# board.net
KiCad netlist of a schematic drawn in EAGLE
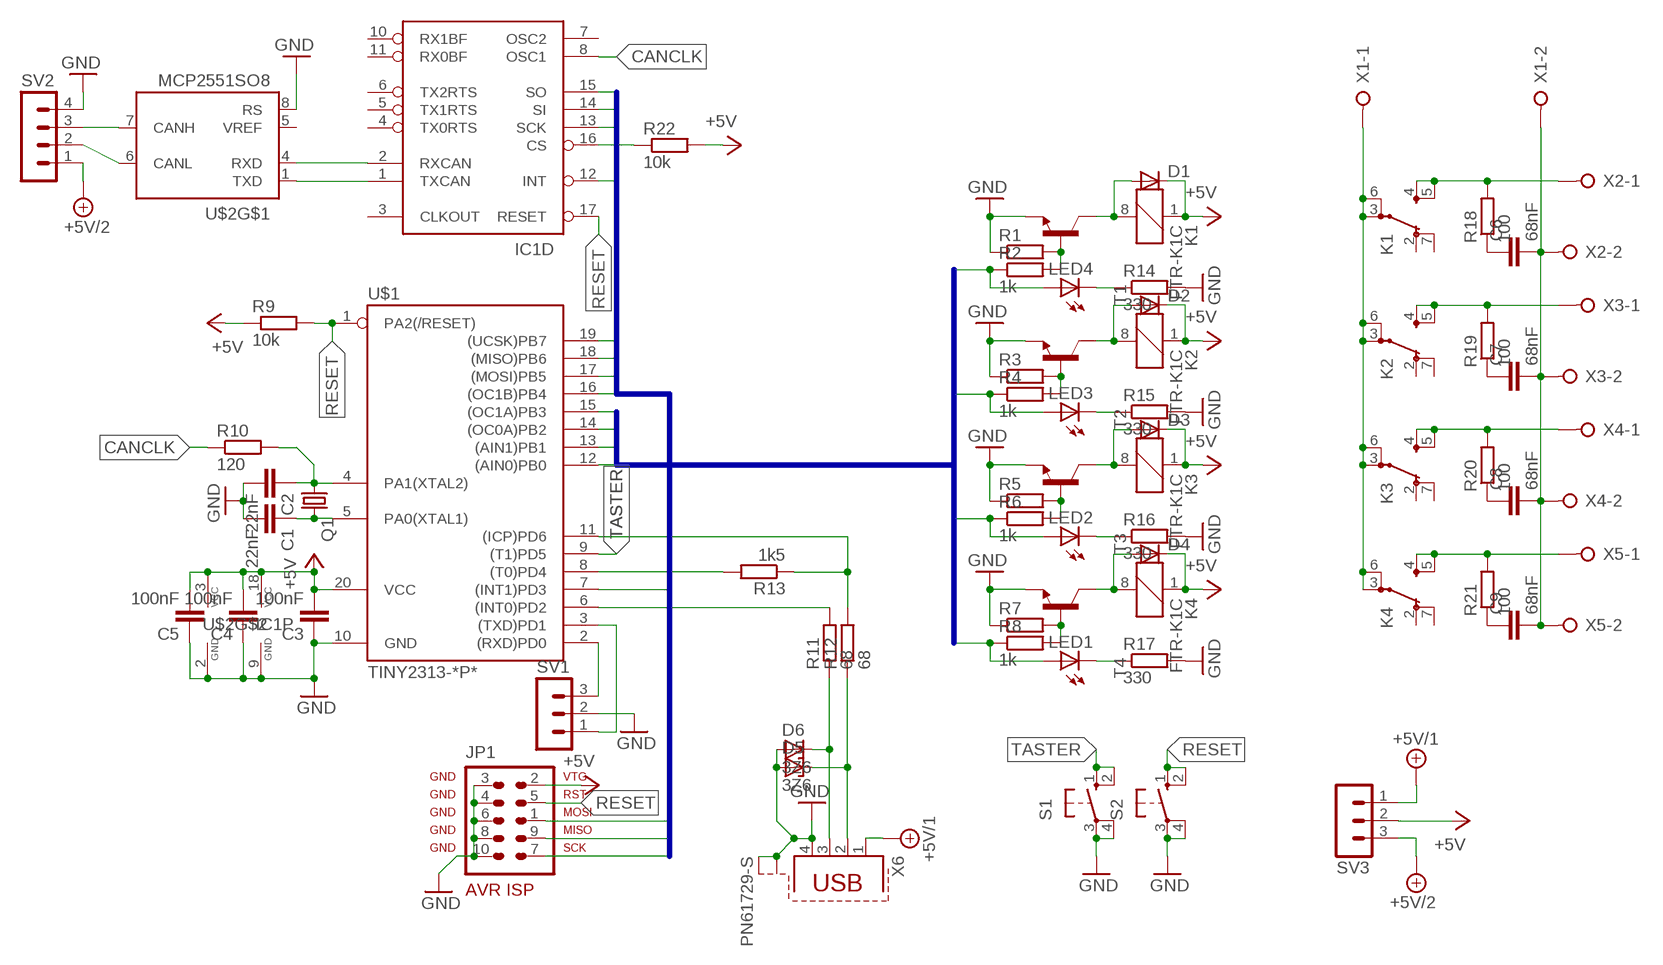
[diagram p0: schematic, sheet 1]

(export (version "E")
  (design (tool "Eeschema 10.0.6"))
  (components
    (comp (ref "C1")
      (value "22nF")
      (footprint "eagle-import:C0805")
      (libsource (lib "eagle-import") (part "C-EUC0805"))
    )
    (comp (ref "C2")
      (value "22nF")
      (footprint "eagle-import:C0805")
      (libsource (lib "eagle-import") (part "C-EUC0805"))
    )
    (comp (ref "C3")
      (value "100nF")
      (footprint "eagle-import:C0805")
      (libsource (lib "eagle-import") (part "C-EUC0805"))
    )
    (comp (ref "C4")
      (value "100nF")
      (footprint "eagle-import:C0805")
      (libsource (lib "eagle-import") (part "C-EUC0805"))
    )
    (comp (ref "C5")
      (value "100nF")
      (footprint "eagle-import:C0805")
      (libsource (lib "eagle-import") (part "C-EUC0805"))
    )
    (comp (ref "C6")
      (value "68nF")
      (footprint "eagle-import:C150-084X183")
      (libsource (lib "eagle-import") (part "C-EU150-084X183"))
    )
    (comp (ref "C7")
      (value "68nF")
      (footprint "eagle-import:C150-084X183")
      (libsource (lib "eagle-import") (part "C-EU150-084X183"))
    )
    (comp (ref "C8")
      (value "68nF")
      (footprint "eagle-import:C150-084X183")
      (libsource (lib "eagle-import") (part "C-EU150-084X183"))
    )
    (comp (ref "C9")
      (value "68nF")
      (footprint "eagle-import:C150-084X183")
      (libsource (lib "eagle-import") (part "C-EU150-084X183"))
    )
    (comp (ref "D1")
      (value "DIODE-DO-214AC")
      (footprint "eagle-import:DO-214AC")
      (libsource (lib "eagle-import") (part "DIODE-DO-214AC"))
    )
    (comp (ref "D2")
      (value "DIODE-DO-214AC")
      (footprint "eagle-import:DO-214AC")
      (libsource (lib "eagle-import") (part "DIODE-DO-214AC"))
    )
    (comp (ref "D3")
      (value "DIODE-DO-214AC")
      (footprint "eagle-import:DO-214AC")
      (libsource (lib "eagle-import") (part "DIODE-DO-214AC"))
    )
    (comp (ref "D4")
      (value "DIODE-DO-214AC")
      (footprint "eagle-import:DO-214AC")
      (libsource (lib "eagle-import") (part "DIODE-DO-214AC"))
    )
    (comp (ref "D5")
      (value "3Z6")
      (footprint "eagle-import:SMB")
      (libsource (lib "eagle-import") (part "ZENER-DIODESMB"))
    )
    (comp (ref "D6")
      (value "3Z6")
      (footprint "eagle-import:SMB")
      (libsource (lib "eagle-import") (part "ZENER-DIODESMB"))
    )
    (comp (ref "IC1")
      (value "MCP2515SO")
      (footprint "eagle-import:SO-18W")
      (libsource (lib "eagle-import") (part "MCP2515SO"))
    )
    (comp (ref "JP1")
      (value "AVR-ISP-10")
      (footprint "eagle-import:AVR-ISP-10")
      (libsource (lib "eagle-import") (part "AVR-ISP-10"))
    )
    (comp (ref "K1")
      (value "FTR-K1C")
      (footprint "eagle-import:FTR-K1C")
      (libsource (lib "eagle-import") (part "FTR-K1C"))
    )
    (comp (ref "K2")
      (value "FTR-K1C")
      (footprint "eagle-import:FTR-K1C")
      (libsource (lib "eagle-import") (part "FTR-K1C"))
    )
    (comp (ref "K3")
      (value "FTR-K1C")
      (footprint "eagle-import:FTR-K1C")
      (libsource (lib "eagle-import") (part "FTR-K1C"))
    )
    (comp (ref "K4")
      (value "FTR-K1C")
      (footprint "eagle-import:FTR-K1C")
      (libsource (lib "eagle-import") (part "FTR-K1C"))
    )
    (comp (ref "LED1")
      (value "LED5MM")
      (footprint "eagle-import:LED5MM")
      (libsource (lib "eagle-import") (part "LED5MM"))
    )
    (comp (ref "LED2")
      (value "LED5MM")
      (footprint "eagle-import:LED5MM")
      (libsource (lib "eagle-import") (part "LED5MM"))
    )
    (comp (ref "LED3")
      (value "LED5MM")
      (footprint "eagle-import:LED5MM")
      (libsource (lib "eagle-import") (part "LED5MM"))
    )
    (comp (ref "LED4")
      (value "LED5MM")
      (footprint "eagle-import:LED5MM")
      (libsource (lib "eagle-import") (part "LED5MM"))
    )
    (comp (ref "Q1")
      (value "CRYSTALHC49U70")
      (footprint "eagle-import:HC49U70")
      (libsource (lib "eagle-import") (part "CRYSTALHC49U70"))
    )
    (comp (ref "R1")
      (value "R-EU_M0805")
      (footprint "eagle-import:M0805")
      (libsource (lib "eagle-import") (part "R-EU_M0805"))
    )
    (comp (ref "R2")
      (value "1k")
      (footprint "eagle-import:M0805")
      (libsource (lib "eagle-import") (part "R-EU_M0805"))
    )
    (comp (ref "R3")
      (value "R-EU_M0805")
      (footprint "eagle-import:M0805")
      (libsource (lib "eagle-import") (part "R-EU_M0805"))
    )
    (comp (ref "R4")
      (value "1k")
      (footprint "eagle-import:M0805")
      (libsource (lib "eagle-import") (part "R-EU_M0805"))
    )
    (comp (ref "R5")
      (value "R-EU_M0805")
      (footprint "eagle-import:M0805")
      (libsource (lib "eagle-import") (part "R-EU_M0805"))
    )
    (comp (ref "R6")
      (value "1k")
      (footprint "eagle-import:M0805")
      (libsource (lib "eagle-import") (part "R-EU_M0805"))
    )
    (comp (ref "R7")
      (value "R-EU_M0805")
      (footprint "eagle-import:M0805")
      (libsource (lib "eagle-import") (part "R-EU_M0805"))
    )
    (comp (ref "R8")
      (value "1k")
      (footprint "eagle-import:M0805")
      (libsource (lib "eagle-import") (part "R-EU_M0805"))
    )
    (comp (ref "R9")
      (value "10k")
      (footprint "eagle-import:M0805")
      (libsource (lib "eagle-import") (part "R-EU_M0805"))
    )
    (comp (ref "R10")
      (value "120")
      (footprint "eagle-import:M0805")
      (libsource (lib "eagle-import") (part "R-EU_M0805"))
    )
    (comp (ref "R11")
      (value "68")
      (footprint "eagle-import:M0805")
      (libsource (lib "eagle-import") (part "R-EU_M0805"))
    )
    (comp (ref "R12")
      (value "68")
      (footprint "eagle-import:M0805")
      (libsource (lib "eagle-import") (part "R-EU_M0805"))
    )
    (comp (ref "R13")
      (value "1k5")
      (footprint "eagle-import:M0805")
      (libsource (lib "eagle-import") (part "R-EU_M0805"))
    )
    (comp (ref "R14")
      (value "330")
      (footprint "eagle-import:M0805")
      (libsource (lib "eagle-import") (part "R-EU_M0805"))
    )
    (comp (ref "R15")
      (value "330")
      (footprint "eagle-import:M0805")
      (libsource (lib "eagle-import") (part "R-EU_M0805"))
    )
    (comp (ref "R16")
      (value "330")
      (footprint "eagle-import:M0805")
      (libsource (lib "eagle-import") (part "R-EU_M0805"))
    )
    (comp (ref "R17")
      (value "330")
      (footprint "eagle-import:M0805")
      (libsource (lib "eagle-import") (part "R-EU_M0805"))
    )
    (comp (ref "R18")
      (value "100")
      (footprint "eagle-import:P0613_15")
      (libsource (lib "eagle-import") (part "R-EU_0613/15"))
    )
    (comp (ref "R19")
      (value "100")
      (footprint "eagle-import:P0613_15")
      (libsource (lib "eagle-import") (part "R-EU_0613/15"))
    )
    (comp (ref "R20")
      (value "100")
      (footprint "eagle-import:P0613_15")
      (libsource (lib "eagle-import") (part "R-EU_0613/15"))
    )
    (comp (ref "R21")
      (value "100")
      (footprint "eagle-import:P0613_15")
      (libsource (lib "eagle-import") (part "R-EU_0613/15"))
    )
    (comp (ref "R22")
      (value "10k")
      (footprint "eagle-import:M0805")
      (libsource (lib "eagle-import") (part "R-EU_M0805"))
    )
    (comp (ref "S1")
      (value "10-XX")
      (footprint "eagle-import:B3F-10XX")
      (fields (field (name "MPN") "B3F-1000"))
      (libsource (lib "eagle-import") (part "10-XX"))
    )
    (comp (ref "S2")
      (value "10-XX")
      (footprint "eagle-import:B3F-10XX")
      (fields (field (name "MPN") "B3F-1000"))
      (libsource (lib "eagle-import") (part "10-XX"))
    )
    (comp (ref "SV1")
      (value "MA03-1")
      (footprint "eagle-import:MA03-1")
      (libsource (lib "eagle-import") (part "MA03-1"))
    )
    (comp (ref "SV2")
      (value "MA04-1")
      (footprint "eagle-import:MA04-1")
      (libsource (lib "eagle-import") (part "MA04-1"))
    )
    (comp (ref "SV3")
      (value "MA03-1")
      (footprint "eagle-import:MA03-1")
      (libsource (lib "eagle-import") (part "MA03-1"))
    )
    (comp (ref "T1")
      (value "-NPN-SOT23-EBC")
      (footprint "eagle-import:SOT23-EBC")
      (libsource (lib "eagle-import") (part "-NPN-SOT23-EBC"))
    )
    (comp (ref "T2")
      (value "-NPN-SOT23-EBC")
      (footprint "eagle-import:SOT23-EBC")
      (libsource (lib "eagle-import") (part "-NPN-SOT23-EBC"))
    )
    (comp (ref "T3")
      (value "-NPN-SOT23-EBC")
      (footprint "eagle-import:SOT23-EBC")
      (libsource (lib "eagle-import") (part "-NPN-SOT23-EBC"))
    )
    (comp (ref "T4")
      (value "-NPN-SOT23-EBC")
      (footprint "eagle-import:SOT23-EBC")
      (libsource (lib "eagle-import") (part "-NPN-SOT23-EBC"))
    )
    (comp (ref "U$1")
      (value "TINY2313-*P*")
      (footprint "eagle-import:DIL20")
      (libsource (lib "eagle-import") (part "TINY2313-P"))
    )
    (comp (ref "U$2")
      (value "MCP2551SO8")
      (footprint "eagle-import:SO08")
      (libsource (lib "eagle-import") (part "MCP2551SO8"))
    )
    (comp (ref "X1")
      (value "W237-02P")
      (footprint "eagle-import:W237-132")
      (libsource (lib "eagle-import") (part "W237-02P"))
    )
    (comp (ref "X2")
      (value "W237-02P")
      (footprint "eagle-import:W237-132")
      (libsource (lib "eagle-import") (part "W237-02P"))
    )
    (comp (ref "X3")
      (value "W237-02P")
      (footprint "eagle-import:W237-132")
      (libsource (lib "eagle-import") (part "W237-02P"))
    )
    (comp (ref "X4")
      (value "W237-02P")
      (footprint "eagle-import:W237-132")
      (libsource (lib "eagle-import") (part "W237-02P"))
    )
    (comp (ref "X5")
      (value "W237-02P")
      (footprint "eagle-import:W237-132")
      (libsource (lib "eagle-import") (part "W237-02P"))
    )
    (comp (ref "X6")
      (value "PN61729-S")
      (footprint "eagle-import:PN61729-S")
      (libsource (lib "eagle-import") (part "PN61729-S"))
    )
  )
  (nets
    (net (code "1") (name "+5V") (class "Default")
      (node (ref "C3") (pin "2") (pinfunction "2_2") (pintype "passive"))
      (node (ref "C4") (pin "2") (pinfunction "2_2") (pintype "passive"))
      (node (ref "C5") (pin "2") (pinfunction "2_2") (pintype "passive"))
      (node (ref "D1") (pin "C") (pinfunction "C_C") (pintype "passive"))
      (node (ref "D2") (pin "C") (pinfunction "C_C") (pintype "passive"))
      (node (ref "D3") (pin "C") (pinfunction "C_C") (pintype "passive"))
      (node (ref "D4") (pin "C") (pinfunction "C_C") (pintype "passive"))
      (node (ref "IC1") (pin "18") (pinfunction "VCC_18") (pintype "power_in"))
      (node (ref "JP1") (pin "2") (pinfunction "2_2") (pintype "passive"))
      (node (ref "K1") (pin "1") (pinfunction "1_1") (pintype "passive"))
      (node (ref "K2") (pin "1") (pinfunction "1_1") (pintype "passive"))
      (node (ref "K3") (pin "1") (pinfunction "1_1") (pintype "passive"))
      (node (ref "K4") (pin "1") (pinfunction "1_1") (pintype "passive"))
      (node (ref "R22") (pin "2") (pinfunction "2_2") (pintype "passive"))
      (node (ref "R9") (pin "1") (pinfunction "1_1") (pintype "passive"))
      (node (ref "SV3") (pin "2") (pinfunction "2_2") (pintype "passive"))
      (node (ref "U$1") (pin "20") (pinfunction "VCC_20") (pintype "power_in"))
      (node (ref "U$2") (pin "3") (pinfunction "VCC_3") (pintype "power_in"))
    )
    (net (code "2") (name "+5V{slash}1") (class "Default")
      (node (ref "SV3") (pin "1") (pinfunction "1_1") (pintype "passive"))
      (node (ref "X6") (pin "1") (pinfunction "1_1") (pintype "passive"))
    )
    (net (code "3") (name "+5V{slash}2") (class "Default")
      (node (ref "SV2") (pin "1") (pinfunction "1_1") (pintype "passive"))
      (node (ref "SV3") (pin "3") (pinfunction "3_3") (pintype "passive"))
    )
    (net (code "4") (name "/CS") (class "Default")
      (node (ref "IC1") (pin "16") (pinfunction "CS_16") (pintype "input"))
      (node (ref "R22") (pin "1") (pinfunction "1_1") (pintype "passive"))
      (node (ref "U$1") (pin "16") (pinfunction "(OC1B)PB4_16") (pintype "bidirectional"))
    )
    (net (code "5") (name "/INT") (class "Default")
      (node (ref "IC1") (pin "12") (pinfunction "INT_12") (pintype "output"))
      (node (ref "U$1") (pin "7") (pinfunction "(INT1)PD3_7") (pintype "bidirectional"))
    )
    (net (code "6") (name "/MISO") (class "Default")
      (node (ref "IC1") (pin "15") (pinfunction "SO_15") (pintype "output"))
      (node (ref "JP1") (pin "9") (pinfunction "9_9") (pintype "passive"))
      (node (ref "U$1") (pin "18") (pinfunction "(MISO)PB6_18") (pintype "bidirectional"))
    )
    (net (code "7") (name "/MOSI") (class "Default")
      (node (ref "IC1") (pin "14") (pinfunction "SI_14") (pintype "input"))
      (node (ref "JP1") (pin "1") (pinfunction "1_1") (pintype "passive"))
      (node (ref "U$1") (pin "17") (pinfunction "(MOSI)PB5_17") (pintype "bidirectional"))
    )
    (net (code "8") (name "/RELAI0") (class "Default")
      (node (ref "LED1") (pin "A") (pinfunction "A_A") (pintype "passive"))
      (node (ref "R8") (pin "1") (pinfunction "1_1") (pintype "passive"))
      (node (ref "U$1") (pin "12") (pinfunction "(AIN0)PB0_12") (pintype "bidirectional"))
    )
    (net (code "9") (name "/RELAI1") (class "Default")
      (node (ref "LED2") (pin "A") (pinfunction "A_A") (pintype "passive"))
      (node (ref "R6") (pin "1") (pinfunction "1_1") (pintype "passive"))
      (node (ref "U$1") (pin "13") (pinfunction "(AIN1)PB1_13") (pintype "bidirectional"))
    )
    (net (code "10") (name "/RELAI2") (class "Default")
      (node (ref "LED3") (pin "A") (pinfunction "A_A") (pintype "passive"))
      (node (ref "R4") (pin "1") (pinfunction "1_1") (pintype "passive"))
      (node (ref "U$1") (pin "14") (pinfunction "(OC0A)PB2_14") (pintype "bidirectional"))
    )
    (net (code "11") (name "/RELAI3") (class "Default")
      (node (ref "LED4") (pin "A") (pinfunction "A_A") (pintype "passive"))
      (node (ref "R2") (pin "1") (pinfunction "1_1") (pintype "passive"))
      (node (ref "U$1") (pin "15") (pinfunction "(OC1A)PB3_15") (pintype "bidirectional"))
    )
    (net (code "12") (name "/SCK") (class "Default")
      (node (ref "IC1") (pin "13") (pinfunction "SCK_13") (pintype "input"))
      (node (ref "JP1") (pin "7") (pinfunction "7_7") (pintype "passive"))
      (node (ref "U$1") (pin "19") (pinfunction "(UCSK)PB7_19") (pintype "bidirectional"))
    )
    (net (code "13") (name "CANCLK") (class "Default")
      (node (ref "IC1") (pin "8") (pinfunction "OSC1_8") (pintype "input"))
      (node (ref "R10") (pin "1") (pinfunction "1_1") (pintype "passive"))
    )
    (net (code "14") (name "GND") (class "Default")
      (node (ref "C1") (pin "2") (pinfunction "2_2") (pintype "passive"))
      (node (ref "C2") (pin "2") (pinfunction "2_2") (pintype "passive"))
      (node (ref "C3") (pin "1") (pinfunction "1_1") (pintype "passive"))
      (node (ref "C4") (pin "1") (pinfunction "1_1") (pintype "passive"))
      (node (ref "C5") (pin "1") (pinfunction "1_1") (pintype "passive"))
      (node (ref "D5") (pin "A") (pinfunction "A_A") (pintype "passive"))
      (node (ref "D6") (pin "A") (pinfunction "A_A") (pintype "passive"))
      (node (ref "IC1") (pin "9") (pinfunction "GND_9") (pintype "power_in"))
      (node (ref "JP1") (pin "10") (pinfunction "10_10") (pintype "passive"))
      (node (ref "JP1") (pin "3") (pinfunction "3_3") (pintype "passive"))
      (node (ref "JP1") (pin "4") (pinfunction "4_4") (pintype "passive"))
      (node (ref "JP1") (pin "6") (pinfunction "6_6") (pintype "passive"))
      (node (ref "JP1") (pin "8") (pinfunction "8_8") (pintype "passive"))
      (node (ref "R1") (pin "1") (pinfunction "1_1") (pintype "passive"))
      (node (ref "R14") (pin "2") (pinfunction "2_2") (pintype "passive"))
      (node (ref "R15") (pin "2") (pinfunction "2_2") (pintype "passive"))
      (node (ref "R16") (pin "2") (pinfunction "2_2") (pintype "passive"))
      (node (ref "R17") (pin "2") (pinfunction "2_2") (pintype "passive"))
      (node (ref "R3") (pin "1") (pinfunction "1_1") (pintype "passive"))
      (node (ref "R5") (pin "1") (pinfunction "1_1") (pintype "passive"))
      (node (ref "R7") (pin "1") (pinfunction "1_1") (pintype "passive"))
      (node (ref "S1") (pin "3") (pinfunction "P_3") (pintype "passive"))
      (node (ref "S1") (pin "4") (pinfunction "P1_4") (pintype "passive"))
      (node (ref "S2") (pin "3") (pinfunction "P_3") (pintype "passive"))
      (node (ref "S2") (pin "4") (pinfunction "P1_4") (pintype "passive"))
      (node (ref "SV1") (pin "2") (pinfunction "2_2") (pintype "passive"))
      (node (ref "SV2") (pin "4") (pinfunction "4_4") (pintype "passive"))
      (node (ref "T1") (pin "E") (pinfunction "E_E") (pintype "passive"))
      (node (ref "T2") (pin "E") (pinfunction "E_E") (pintype "passive"))
      (node (ref "T3") (pin "E") (pinfunction "E_E") (pintype "passive"))
      (node (ref "T4") (pin "E") (pinfunction "E_E") (pintype "passive"))
      (node (ref "U$1") (pin "10") (pinfunction "GND_10") (pintype "power_in"))
      (node (ref "U$2") (pin "2") (pinfunction "GND_2") (pintype "power_in"))
      (node (ref "U$2") (pin "8") (pinfunction "RS_8") (pintype "bidirectional"))
      (node (ref "X6") (pin "4") (pinfunction "4_4") (pintype "passive"))
      (node (ref "X6") (pin "S1") (pinfunction "S1_S1") (pintype "passive"))
      (node (ref "X6") (pin "S2") (pinfunction "S2_S2") (pintype "passive"))
    )
    (net (code "15") (name "Net-(C6-Pad1)") (class "Default")
      (node (ref "C6") (pin "1") (pinfunction "1_1") (pintype "passive"))
      (node (ref "R18") (pin "1") (pinfunction "1_1") (pintype "passive"))
    )
    (net (code "16") (name "Net-(C7-Pad1)") (class "Default")
      (node (ref "C7") (pin "1") (pinfunction "1_1") (pintype "passive"))
      (node (ref "R19") (pin "1") (pinfunction "1_1") (pintype "passive"))
    )
    (net (code "17") (name "Net-(C8-Pad1)") (class "Default")
      (node (ref "C8") (pin "1") (pinfunction "1_1") (pintype "passive"))
      (node (ref "R20") (pin "1") (pinfunction "1_1") (pintype "passive"))
    )
    (net (code "18") (name "Net-(C9-Pad1)") (class "Default")
      (node (ref "C9") (pin "1") (pinfunction "1_1") (pintype "passive"))
      (node (ref "R21") (pin "1") (pinfunction "1_1") (pintype "passive"))
    )
    (net (code "19") (name "Net-(D5-PadC)") (class "Default")
      (node (ref "D5") (pin "C") (pinfunction "C_C") (pintype "passive"))
      (node (ref "R12") (pin "1") (pinfunction "1_1") (pintype "passive"))
      (node (ref "X6") (pin "2") (pinfunction "2_2") (pintype "passive"))
    )
    (net (code "20") (name "Net-(D6-PadC)") (class "Default")
      (node (ref "D6") (pin "C") (pinfunction "C_C") (pintype "passive"))
      (node (ref "R11") (pin "1") (pinfunction "1_1") (pintype "passive"))
      (node (ref "X6") (pin "3") (pinfunction "3_3") (pintype "passive"))
    )
    (net (code "21") (name "Net-(IC1A-RXCAN)") (class "Default")
      (node (ref "IC1") (pin "2") (pinfunction "RXCAN_2") (pintype "input"))
      (node (ref "U$2") (pin "4") (pinfunction "RXD_4") (pintype "bidirectional"))
    )
    (net (code "22") (name "Net-(IC1A-TXCAN)") (class "Default")
      (node (ref "IC1") (pin "1") (pinfunction "TXCAN_1") (pintype "output"))
      (node (ref "U$2") (pin "1") (pinfunction "TXD_1") (pintype "bidirectional"))
    )
    (net (code "23") (name "Net-(K1A-PA)") (class "Default")
      (node (ref "K1") (pin "3") (pinfunction "PA_3") (pintype "passive"))
      (node (ref "K1") (pin "6") (pinfunction "PB_6") (pintype "passive"))
      (node (ref "K2") (pin "3") (pinfunction "PA_3") (pintype "passive"))
      (node (ref "K2") (pin "6") (pinfunction "PB_6") (pintype "passive"))
      (node (ref "K3") (pin "3") (pinfunction "PA_3") (pintype "passive"))
      (node (ref "K3") (pin "6") (pinfunction "PB_6") (pintype "passive"))
      (node (ref "K4") (pin "3") (pinfunction "PA_3") (pintype "passive"))
      (node (ref "K4") (pin "6") (pinfunction "PB_6") (pintype "passive"))
      (node (ref "X1") (pin "1") (pinfunction "KL_1") (pintype "passive"))
    )
    (net (code "24") (name "Net-(K1A-SA)") (class "Default")
      (node (ref "K1") (pin "4") (pinfunction "SA_4") (pintype "passive"))
      (node (ref "K1") (pin "5") (pinfunction "SB_5") (pintype "passive"))
      (node (ref "R18") (pin "2") (pinfunction "2_2") (pintype "passive"))
      (node (ref "X2") (pin "1") (pinfunction "KL_1") (pintype "passive"))
    )
    (net (code "25") (name "Net-(K1B-2)") (class "Default")
      (node (ref "D1") (pin "A") (pinfunction "A_A") (pintype "passive"))
      (node (ref "K1") (pin "8") (pinfunction "2_8") (pintype "passive"))
      (node (ref "T1") (pin "C") (pinfunction "C_C") (pintype "passive"))
    )
    (net (code "26") (name "Net-(K2A-SA)") (class "Default")
      (node (ref "K2") (pin "4") (pinfunction "SA_4") (pintype "passive"))
      (node (ref "K2") (pin "5") (pinfunction "SB_5") (pintype "passive"))
      (node (ref "R19") (pin "2") (pinfunction "2_2") (pintype "passive"))
      (node (ref "X3") (pin "1") (pinfunction "KL_1") (pintype "passive"))
    )
    (net (code "27") (name "Net-(K2B-2)") (class "Default")
      (node (ref "D2") (pin "A") (pinfunction "A_A") (pintype "passive"))
      (node (ref "K2") (pin "8") (pinfunction "2_8") (pintype "passive"))
      (node (ref "T2") (pin "C") (pinfunction "C_C") (pintype "passive"))
    )
    (net (code "28") (name "Net-(K3A-SA)") (class "Default")
      (node (ref "K3") (pin "4") (pinfunction "SA_4") (pintype "passive"))
      (node (ref "K3") (pin "5") (pinfunction "SB_5") (pintype "passive"))
      (node (ref "R20") (pin "2") (pinfunction "2_2") (pintype "passive"))
      (node (ref "X4") (pin "1") (pinfunction "KL_1") (pintype "passive"))
    )
    (net (code "29") (name "Net-(K3B-2)") (class "Default")
      (node (ref "D3") (pin "A") (pinfunction "A_A") (pintype "passive"))
      (node (ref "K3") (pin "8") (pinfunction "2_8") (pintype "passive"))
      (node (ref "T3") (pin "C") (pinfunction "C_C") (pintype "passive"))
    )
    (net (code "30") (name "Net-(K4A-SA)") (class "Default")
      (node (ref "K4") (pin "4") (pinfunction "SA_4") (pintype "passive"))
      (node (ref "K4") (pin "5") (pinfunction "SB_5") (pintype "passive"))
      (node (ref "R21") (pin "2") (pinfunction "2_2") (pintype "passive"))
      (node (ref "X5") (pin "1") (pinfunction "KL_1") (pintype "passive"))
    )
    (net (code "31") (name "Net-(K4B-2)") (class "Default")
      (node (ref "D4") (pin "A") (pinfunction "A_A") (pintype "passive"))
      (node (ref "K4") (pin "8") (pinfunction "2_8") (pintype "passive"))
      (node (ref "T4") (pin "C") (pinfunction "C_C") (pintype "passive"))
    )
    (net (code "32") (name "Net-(LED1-C)") (class "Default")
      (node (ref "LED1") (pin "K") (pinfunction "C_K") (pintype "passive"))
      (node (ref "R17") (pin "1") (pinfunction "1_1") (pintype "passive"))
    )
    (net (code "33") (name "Net-(LED2-C)") (class "Default")
      (node (ref "LED2") (pin "K") (pinfunction "C_K") (pintype "passive"))
      (node (ref "R16") (pin "1") (pinfunction "1_1") (pintype "passive"))
    )
    (net (code "34") (name "Net-(LED3-C)") (class "Default")
      (node (ref "LED3") (pin "K") (pinfunction "C_K") (pintype "passive"))
      (node (ref "R15") (pin "1") (pinfunction "1_1") (pintype "passive"))
    )
    (net (code "35") (name "Net-(LED4-C)") (class "Default")
      (node (ref "LED4") (pin "K") (pinfunction "C_K") (pintype "passive"))
      (node (ref "R14") (pin "1") (pinfunction "1_1") (pintype "passive"))
    )
    (net (code "36") (name "Net-(R1-Pad2)") (class "Default")
      (node (ref "R1") (pin "2") (pinfunction "2_2") (pintype "passive"))
      (node (ref "R2") (pin "2") (pinfunction "2_2") (pintype "passive"))
      (node (ref "T1") (pin "B") (pinfunction "B_B") (pintype "passive"))
    )
    (net (code "37") (name "Net-(R3-Pad2)") (class "Default")
      (node (ref "R3") (pin "2") (pinfunction "2_2") (pintype "passive"))
      (node (ref "R4") (pin "2") (pinfunction "2_2") (pintype "passive"))
      (node (ref "T2") (pin "B") (pinfunction "B_B") (pintype "passive"))
    )
    (net (code "38") (name "Net-(R5-Pad2)") (class "Default")
      (node (ref "R5") (pin "2") (pinfunction "2_2") (pintype "passive"))
      (node (ref "R6") (pin "2") (pinfunction "2_2") (pintype "passive"))
      (node (ref "T3") (pin "B") (pinfunction "B_B") (pintype "passive"))
    )
    (net (code "39") (name "Net-(R7-Pad2)") (class "Default")
      (node (ref "R7") (pin "2") (pinfunction "2_2") (pintype "passive"))
      (node (ref "R8") (pin "2") (pinfunction "2_2") (pintype "passive"))
      (node (ref "T4") (pin "B") (pinfunction "B_B") (pintype "passive"))
    )
    (net (code "40") (name "Net-(U$1-(ICP)PD6)") (class "Default")
      (node (ref "R12") (pin "2") (pinfunction "2_2") (pintype "passive"))
      (node (ref "R13") (pin "1") (pinfunction "1_1") (pintype "passive"))
      (node (ref "U$1") (pin "11") (pinfunction "(ICP)PD6_11") (pintype "bidirectional"))
    )
    (net (code "41") (name "Net-(U$1-(INT0)PD2)") (class "Default")
      (node (ref "R11") (pin "2") (pinfunction "2_2") (pintype "passive"))
      (node (ref "U$1") (pin "6") (pinfunction "(INT0)PD2_6") (pintype "bidirectional"))
    )
    (net (code "42") (name "Net-(U$1-(RXD)PD0)") (class "Default")
      (node (ref "SV1") (pin "3") (pinfunction "3_3") (pintype "passive"))
      (node (ref "U$1") (pin "2") (pinfunction "(RXD)PD0_2") (pintype "bidirectional"))
    )
    (net (code "43") (name "Net-(U$1-(T0)PD4)") (class "Default")
      (node (ref "R13") (pin "2") (pinfunction "2_2") (pintype "passive"))
      (node (ref "U$1") (pin "8") (pinfunction "(T0)PD4_8") (pintype "bidirectional"))
    )
    (net (code "44") (name "Net-(U$1-(TXD)PD1)") (class "Default")
      (node (ref "SV1") (pin "1") (pinfunction "1_1") (pintype "passive"))
      (node (ref "U$1") (pin "3") (pinfunction "(TXD)PD1_3") (pintype "bidirectional"))
    )
    (net (code "45") (name "Net-(U$1-PA0(XTAL1))") (class "Default")
      (node (ref "C1") (pin "1") (pinfunction "1_1") (pintype "passive"))
      (node (ref "Q1") (pin "2") (pinfunction "2_2") (pintype "passive"))
      (node (ref "U$1") (pin "5") (pinfunction "PA0(XTAL1)_5") (pintype "bidirectional"))
    )
    (net (code "46") (name "Net-(U$1-PA1(XTAL2))") (class "Default")
      (node (ref "C2") (pin "1") (pinfunction "1_1") (pintype "passive"))
      (node (ref "Q1") (pin "1") (pinfunction "1_1") (pintype "passive"))
      (node (ref "R10") (pin "2") (pinfunction "2_2") (pintype "passive"))
      (node (ref "U$1") (pin "4") (pinfunction "PA1(XTAL2)_4") (pintype "bidirectional"))
    )
    (net (code "47") (name "Net-(U$2A-CANH)") (class "Default")
      (node (ref "SV2") (pin "3") (pinfunction "3_3") (pintype "passive"))
      (node (ref "U$2") (pin "7") (pinfunction "CANH_7") (pintype "bidirectional"))
    )
    (net (code "48") (name "Net-(U$2A-CANL)") (class "Default")
      (node (ref "SV2") (pin "2") (pinfunction "2_2") (pintype "passive"))
      (node (ref "U$2") (pin "6") (pinfunction "CANL_6") (pintype "bidirectional"))
    )
    (net (code "49") (name "Net-(X1B-KL)") (class "Default")
      (node (ref "C6") (pin "2") (pinfunction "2_2") (pintype "passive"))
      (node (ref "C7") (pin "2") (pinfunction "2_2") (pintype "passive"))
      (node (ref "C8") (pin "2") (pinfunction "2_2") (pintype "passive"))
      (node (ref "C9") (pin "2") (pinfunction "2_2") (pintype "passive"))
      (node (ref "X1") (pin "2") (pinfunction "KL_2") (pintype "passive"))
      (node (ref "X2") (pin "2") (pinfunction "KL_2") (pintype "passive"))
      (node (ref "X3") (pin "2") (pinfunction "KL_2") (pintype "passive"))
      (node (ref "X4") (pin "2") (pinfunction "KL_2") (pintype "passive"))
      (node (ref "X5") (pin "2") (pinfunction "KL_2") (pintype "passive"))
    )
    (net (code "50") (name "RESET") (class "Default")
      (node (ref "IC1") (pin "17") (pinfunction "RESET_17") (pintype "input"))
      (node (ref "JP1") (pin "5") (pinfunction "5_5") (pintype "passive"))
      (node (ref "R9") (pin "2") (pinfunction "2_2") (pintype "passive"))
      (node (ref "S2") (pin "1") (pinfunction "S_1") (pintype "passive"))
      (node (ref "S2") (pin "2") (pinfunction "S1_2") (pintype "passive"))
      (node (ref "U$1") (pin "1") (pinfunction "PA2(/RESET)_1") (pintype "input"))
    )
    (net (code "51") (name "TASTER") (class "Default")
      (node (ref "S1") (pin "1") (pinfunction "S_1") (pintype "passive"))
      (node (ref "S1") (pin "2") (pinfunction "S1_2") (pintype "passive"))
      (node (ref "U$1") (pin "9") (pinfunction "(T1)PD5_9") (pintype "bidirectional"))
    )
    (net (code "52") (name "unconnected-(IC1A-CLKOUT-Pad3)") (class "Default")
      (node (ref "IC1") (pin "3") (pinfunction "CLKOUT_3") (pintype "output"))
    )
    (net (code "53") (name "unconnected-(IC1A-OSC2-Pad7)") (class "Default")
      (node (ref "IC1") (pin "7") (pinfunction "OSC2_7") (pintype "input"))
    )
    (net (code "54") (name "unconnected-(IC1A-RX0BF-Pad11)") (class "Default")
      (node (ref "IC1") (pin "11") (pinfunction "RX0BF_11") (pintype "output"))
    )
    (net (code "55") (name "unconnected-(IC1A-RX1BF-Pad10)") (class "Default")
      (node (ref "IC1") (pin "10") (pinfunction "RX1BF_10") (pintype "output"))
    )
    (net (code "56") (name "unconnected-(IC1A-TX0RTS-Pad4)") (class "Default")
      (node (ref "IC1") (pin "4") (pinfunction "TX0RTS_4") (pintype "input"))
    )
    (net (code "57") (name "unconnected-(IC1A-TX1RTS-Pad5)") (class "Default")
      (node (ref "IC1") (pin "5") (pinfunction "TX1RTS_5") (pintype "input"))
    )
    (net (code "58") (name "unconnected-(IC1A-TX2RTS-Pad6)") (class "Default")
      (node (ref "IC1") (pin "6") (pinfunction "TX2RTS_6") (pintype "input"))
    )
    (net (code "59") (name "unconnected-(K1A-OA-Pad2)") (class "Default")
      (node (ref "K1") (pin "2") (pinfunction "OA_2") (pintype "passive"))
    )
    (net (code "60") (name "unconnected-(K1A-OB-Pad7)") (class "Default")
      (node (ref "K1") (pin "7") (pinfunction "OB_7") (pintype "passive"))
    )
    (net (code "61") (name "unconnected-(K2A-OA-Pad2)") (class "Default")
      (node (ref "K2") (pin "2") (pinfunction "OA_2") (pintype "passive"))
    )
    (net (code "62") (name "unconnected-(K2A-OB-Pad7)") (class "Default")
      (node (ref "K2") (pin "7") (pinfunction "OB_7") (pintype "passive"))
    )
    (net (code "63") (name "unconnected-(K3A-OA-Pad2)") (class "Default")
      (node (ref "K3") (pin "2") (pinfunction "OA_2") (pintype "passive"))
    )
    (net (code "64") (name "unconnected-(K3A-OB-Pad7)") (class "Default")
      (node (ref "K3") (pin "7") (pinfunction "OB_7") (pintype "passive"))
    )
    (net (code "65") (name "unconnected-(K4A-OA-Pad2)") (class "Default")
      (node (ref "K4") (pin "2") (pinfunction "OA_2") (pintype "passive"))
    )
    (net (code "66") (name "unconnected-(K4A-OB-Pad7)") (class "Default")
      (node (ref "K4") (pin "7") (pinfunction "OB_7") (pintype "passive"))
    )
    (net (code "67") (name "unconnected-(U$2A-VREF-Pad5)") (class "Default")
      (node (ref "U$2") (pin "5") (pinfunction "VREF_5") (pintype "bidirectional"))
    )
  )
)
